# MightyWatt_R3.net
KiCad netlist of a schematic drawn in EAGLE
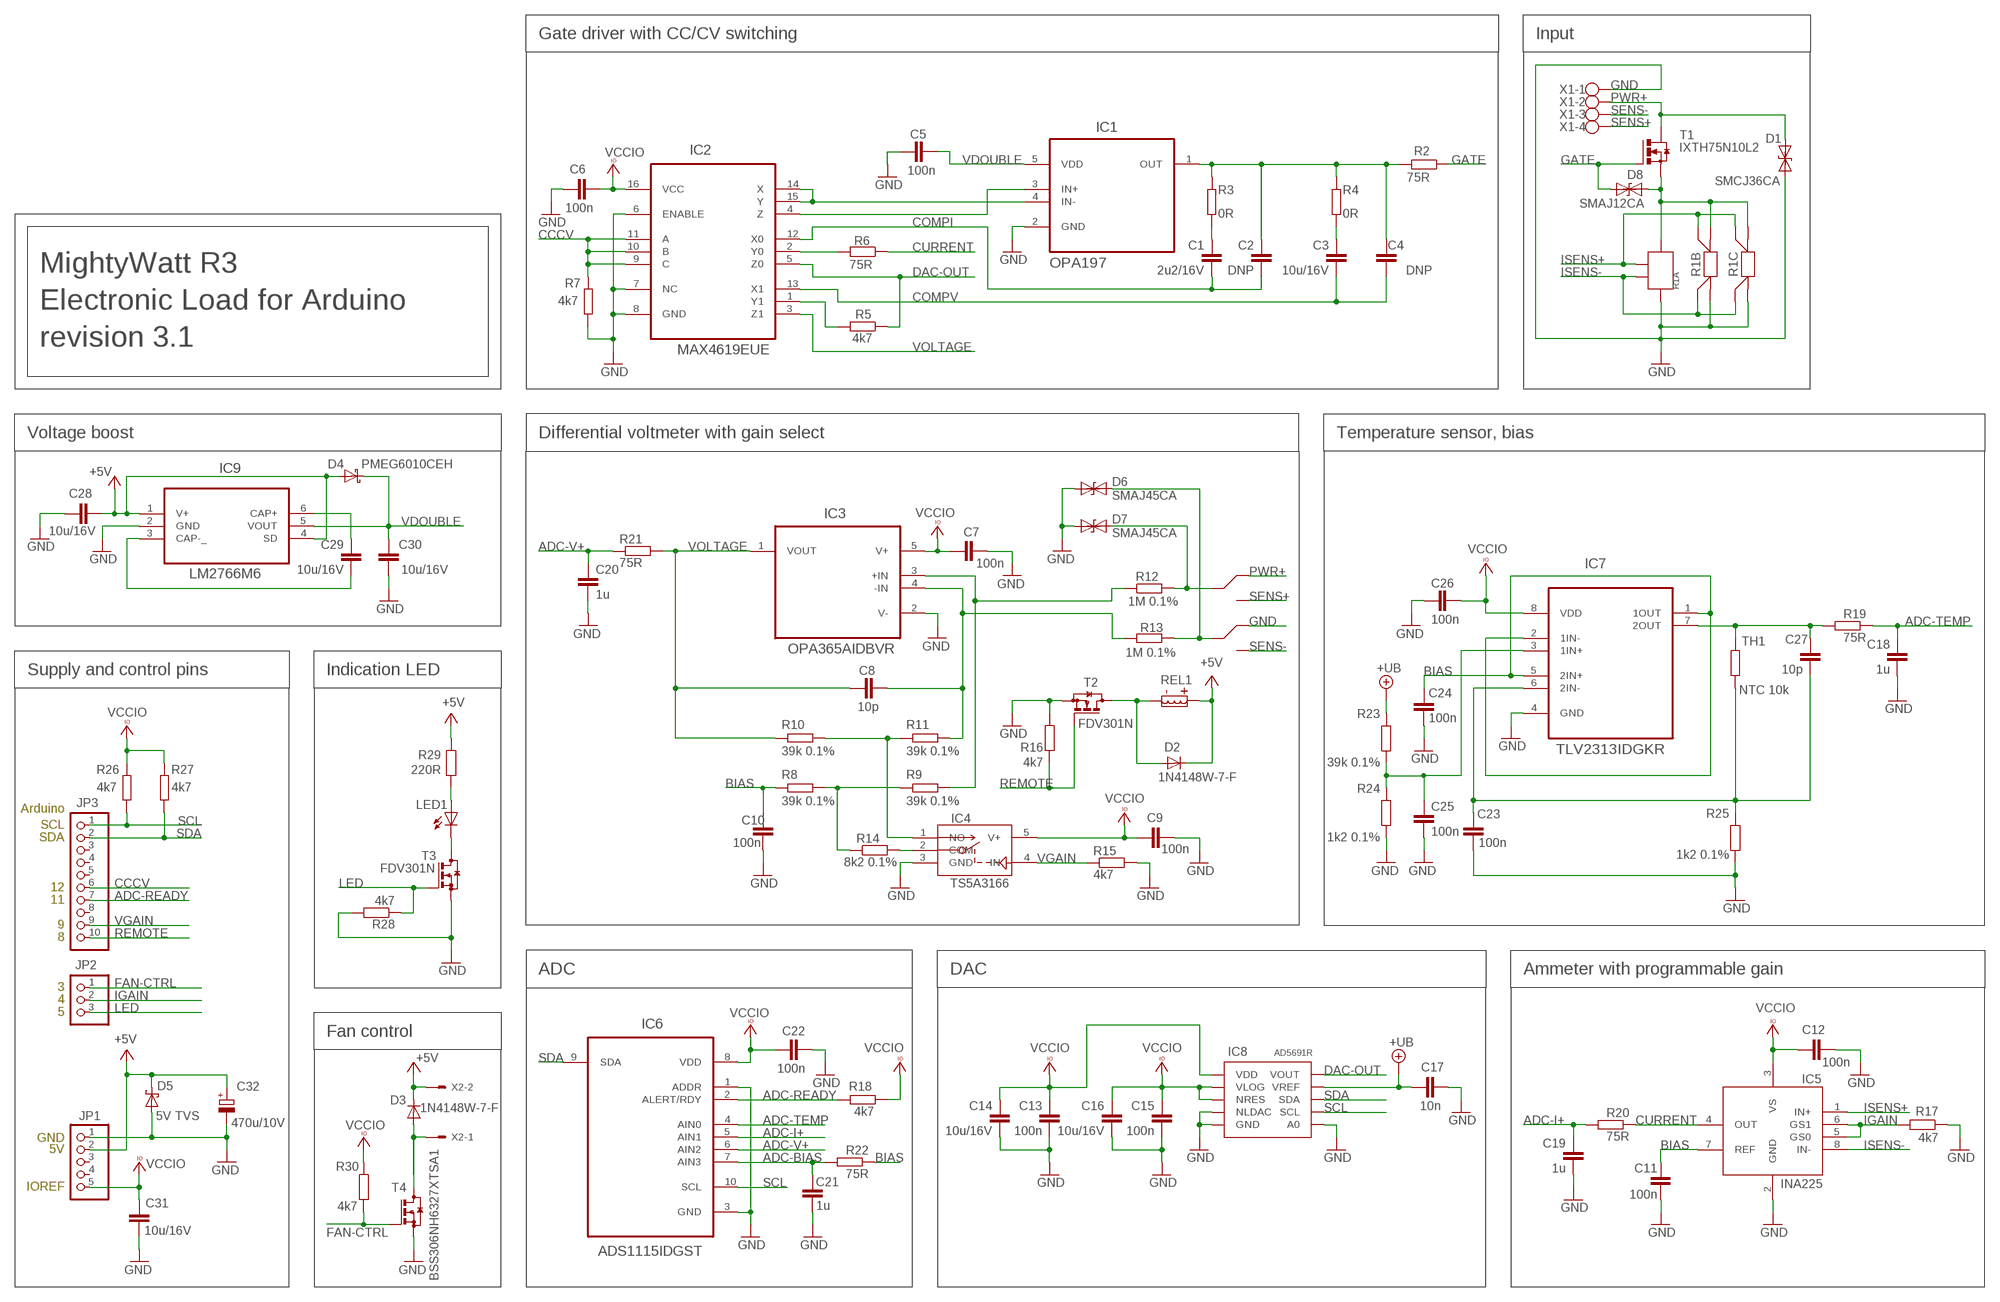
[diagram p0: schematic, sheet 1]

(export (version "E")
  (design (tool "Eeschema 10.0.6"))
  (components
    (comp (ref "C1")
      (value "2u2/16V")
      (footprint "eagle-import:C1206")
      (libsource (lib "eagle-import") (part "C-EUC1206"))
    )
    (comp (ref "C2")
      (value "DNP")
      (footprint "eagle-import:C0603")
      (libsource (lib "eagle-import") (part "C-EUC0603"))
    )
    (comp (ref "C3")
      (value "10u/16V")
      (footprint "eagle-import:C1206")
      (libsource (lib "eagle-import") (part "C-EUC1206"))
    )
    (comp (ref "C4")
      (value "DNP")
      (footprint "eagle-import:C0603")
      (libsource (lib "eagle-import") (part "C-EUC0603"))
    )
    (comp (ref "C5")
      (value "100n")
      (footprint "eagle-import:C0603")
      (libsource (lib "eagle-import") (part "C-EUC0603"))
    )
    (comp (ref "C6")
      (value "100n")
      (footprint "eagle-import:C0603")
      (libsource (lib "eagle-import") (part "C-EUC0603"))
    )
    (comp (ref "C7")
      (value "100n")
      (footprint "eagle-import:C0603")
      (libsource (lib "eagle-import") (part "C-EUC0603"))
    )
    (comp (ref "C8")
      (value "10p")
      (footprint "eagle-import:C0603")
      (libsource (lib "eagle-import") (part "C-EUC0603"))
    )
    (comp (ref "C9")
      (value "100n")
      (footprint "eagle-import:C0603")
      (libsource (lib "eagle-import") (part "C-EUC0603"))
    )
    (comp (ref "C10")
      (value "100n")
      (footprint "eagle-import:C0603")
      (libsource (lib "eagle-import") (part "C-EUC0603"))
    )
    (comp (ref "C11")
      (value "100n")
      (footprint "eagle-import:C0603")
      (libsource (lib "eagle-import") (part "C-EUC0603"))
    )
    (comp (ref "C12")
      (value "100n")
      (footprint "eagle-import:C0603")
      (libsource (lib "eagle-import") (part "C-EUC0603"))
    )
    (comp (ref "C13")
      (value "100n")
      (footprint "eagle-import:C0603")
      (libsource (lib "eagle-import") (part "C-EUC0603"))
    )
    (comp (ref "C14")
      (value "10u/16V")
      (footprint "eagle-import:C1206")
      (libsource (lib "eagle-import") (part "C-EUC1206"))
    )
    (comp (ref "C15")
      (value "100n")
      (footprint "eagle-import:C0603")
      (libsource (lib "eagle-import") (part "C-EUC0603"))
    )
    (comp (ref "C16")
      (value "10u/16V")
      (footprint "eagle-import:C1206")
      (libsource (lib "eagle-import") (part "C-EUC1206"))
    )
    (comp (ref "C17")
      (value "10n")
      (footprint "eagle-import:C0603")
      (libsource (lib "eagle-import") (part "C-EUC0603"))
    )
    (comp (ref "C18")
      (value "1u")
      (footprint "eagle-import:C0603")
      (libsource (lib "eagle-import") (part "C-EUC0603"))
    )
    (comp (ref "C19")
      (value "1u")
      (footprint "eagle-import:C0603")
      (libsource (lib "eagle-import") (part "C-EUC0603"))
    )
    (comp (ref "C20")
      (value "1u")
      (footprint "eagle-import:C0603")
      (libsource (lib "eagle-import") (part "C-EUC0603"))
    )
    (comp (ref "C21")
      (value "1u")
      (footprint "eagle-import:C0603")
      (libsource (lib "eagle-import") (part "C-EUC0603"))
    )
    (comp (ref "C22")
      (value "100n")
      (footprint "eagle-import:C0603")
      (libsource (lib "eagle-import") (part "C-EUC0603"))
    )
    (comp (ref "C23")
      (value "100n")
      (footprint "eagle-import:C0603")
      (libsource (lib "eagle-import") (part "C-EUC0603"))
    )
    (comp (ref "C24")
      (value "100n")
      (footprint "eagle-import:C0603")
      (libsource (lib "eagle-import") (part "C-EUC0603"))
    )
    (comp (ref "C25")
      (value "100n")
      (footprint "eagle-import:C0603")
      (libsource (lib "eagle-import") (part "C-EUC0603"))
    )
    (comp (ref "C26")
      (value "100n")
      (footprint "eagle-import:C0603")
      (libsource (lib "eagle-import") (part "C-EUC0603"))
    )
    (comp (ref "C27")
      (value "10p")
      (footprint "eagle-import:C0603")
      (libsource (lib "eagle-import") (part "C-EUC0603"))
    )
    (comp (ref "C28")
      (value "10u/16V")
      (footprint "eagle-import:C1206")
      (libsource (lib "eagle-import") (part "C-EUC1206"))
    )
    (comp (ref "C29")
      (value "10u/16V")
      (footprint "eagle-import:C1206")
      (libsource (lib "eagle-import") (part "C-EUC1206"))
    )
    (comp (ref "C30")
      (value "10u/16V")
      (footprint "eagle-import:C1206")
      (libsource (lib "eagle-import") (part "C-EUC1206"))
    )
    (comp (ref "C31")
      (value "10u/16V")
      (footprint "eagle-import:C1206")
      (libsource (lib "eagle-import") (part "C-EUC1206"))
    )
    (comp (ref "C32")
      (value "470u/10V")
      (footprint "eagle-import:SMC_E")
      (fields (field (name "PARTN") "TPSB476K010R0250"))
      (libsource (lib "eagle-import") (part "CPOL-EUSMCE"))
    )
    (comp (ref "D1")
      (value "SMCJ36CA")
      (footprint "eagle-import:SMC")
      (libsource (lib "eagle-import") (part "DIODE2SMC"))
    )
    (comp (ref "D2")
      (value "1N4148W-7-F")
      (footprint "eagle-import:SOD123")
      (libsource (lib "eagle-import") (part "DIODE-SOD123"))
    )
    (comp (ref "D3")
      (value "1N4148W-7-F")
      (footprint "eagle-import:SOD123")
      (libsource (lib "eagle-import") (part "DIODE-SOD123"))
    )
    (comp (ref "D4")
      (value "PMEG6010CEH")
      (footprint "eagle-import:SOD123")
      (libsource (lib "eagle-import") (part "diode-schottky_DIODE-SOD123"))
    )
    (comp (ref "D5")
      (value "5V TVS")
      (footprint "eagle-import:SMB")
      (libsource (lib "eagle-import") (part "SCHOTTKY-DIODESMD"))
    )
    (comp (ref "D6")
      (value "SMAJ45CA")
      (footprint "eagle-import:DO-214AC")
      (libsource (lib "eagle-import") (part "DIODE2DO-214AC"))
    )
    (comp (ref "D7")
      (value "SMAJ45CA")
      (footprint "eagle-import:DO-214AC")
      (libsource (lib "eagle-import") (part "DIODE2DO-214AC"))
    )
    (comp (ref "D8")
      (value "SMAJ12CA")
      (footprint "eagle-import:DO-214AC")
      (libsource (lib "eagle-import") (part "DIODE2DO-214AC"))
    )
    (comp (ref "IC1")
      (value "TLV271IDBVR")
      (footprint "eagle-import:SOT95P280X145-5N")
      (fields (field (name "MPN") "TLV271IDBVR") (field (name "MPN_1") "OPA197"))
      (libsource (lib "eagle-import") (part "TLV271IDBVR"))
    )
    (comp (ref "IC2")
      (value "MAX4619EUE")
      (footprint "eagle-import:SOP65P640X120-16N")
      (libsource (lib "eagle-import") (part "MAX4619EUE"))
    )
    (comp (ref "IC3")
      (value "OPA365AIDBVR")
      (footprint "eagle-import:SOT95P280X145-5N")
      (libsource (lib "eagle-import") (part "OPA365AIDBVR"))
    )
    (comp (ref "IC4")
      (value "TS5A3166")
      (footprint "eagle-import:SC70-5")
      (libsource (lib "eagle-import") (part "TS5A3166"))
    )
    (comp (ref "IC5")
      (value "INA225")
      (footprint "eagle-import:MSOP8")
      (libsource (lib "eagle-import") (part "INA225"))
    )
    (comp (ref "IC6")
      (value "ADS1115IDGST")
      (footprint "eagle-import:SOP50P490X110-10N")
      (fields (field (name "MPN") "ADS1015IDGST"))
      (libsource (lib "eagle-import") (part "ADS1115IDGST"))
    )
    (comp (ref "IC7")
      (value "TLV2372IDGK")
      (footprint "eagle-import:SOP65P490X110-8N")
      (fields (field (name "MPN") "TLV2372IDGK") (field (name "MPN_1") "TLV2313IDGKR"))
      (libsource (lib "eagle-import") (part "TLV2372IDGK"))
    )
    (comp (ref "IC8")
      (value "AD5691RAD5691R")
      (footprint "eagle-import:SOP50P490X110-10N")
      (libsource (lib "eagle-import") (part "AD5691RAD5691R"))
    )
    (comp (ref "IC9")
      (value "LM2766M6")
      (footprint "eagle-import:SOT95P285X122-6N")
      (libsource (lib "eagle-import") (part "LM2766M6"))
    )
    (comp (ref "JP1")
      (value "SUPPLY")
      (footprint "eagle-import:1X05")
      (libsource (lib "eagle-import") (part "PINHD-1X5"))
    )
    (comp (ref "JP2")
      (value "CONTROL, LED")
      (footprint "eagle-import:1X03")
      (libsource (lib "eagle-import") (part "PINHD-1X3"))
    )
    (comp (ref "JP3")
      (value "TWI")
      (footprint "eagle-import:1X10")
      (libsource (lib "eagle-import") (part "PINHD-1X10"))
    )
    (comp (ref "LED1")
      (value "LEDCHIP-LED0805")
      (footprint "eagle-import:CHIP-LED0805")
      (libsource (lib "eagle-import") (part "LEDCHIP-LED0805"))
    )
    (comp (ref "R1A")
      (value "WSL3637")
      (footprint "eagle-import:POWER-R-4TERM")
      (libsource (lib "eagle-import") (part "WSL3637"))
    )
    (comp (ref "R1B")
      (value "LVK24")
      (footprint "eagle-import:LVK24")
      (libsource (lib "eagle-import") (part "LVK24"))
    )
    (comp (ref "R1C")
      (value "LVK12")
      (footprint "eagle-import:1206-4WIRE")
      (libsource (lib "eagle-import") (part "LVK12"))
    )
    (comp (ref "R2")
      (value "75R")
      (footprint "eagle-import:R0603")
      (libsource (lib "eagle-import") (part "R-EU_R0603"))
    )
    (comp (ref "R3")
      (value "0R")
      (footprint "eagle-import:R0603")
      (libsource (lib "eagle-import") (part "R-EU_R0603"))
    )
    (comp (ref "R4")
      (value "0R")
      (footprint "eagle-import:R0603")
      (libsource (lib "eagle-import") (part "R-EU_R0603"))
    )
    (comp (ref "R5")
      (value "4k7")
      (footprint "eagle-import:R0603")
      (libsource (lib "eagle-import") (part "R-EU_R0603"))
    )
    (comp (ref "R6")
      (value "75R")
      (footprint "eagle-import:R0603")
      (libsource (lib "eagle-import") (part "R-EU_R0603"))
    )
    (comp (ref "R7")
      (value "4k7")
      (footprint "eagle-import:R0603")
      (libsource (lib "eagle-import") (part "R-EU_R0603"))
    )
    (comp (ref "R8")
      (value "39k 0.1%")
      (footprint "eagle-import:R0603")
      (libsource (lib "eagle-import") (part "R-EU_R0603"))
    )
    (comp (ref "R9")
      (value "39k 0.1%")
      (footprint "eagle-import:R0603")
      (libsource (lib "eagle-import") (part "R-EU_R0603"))
    )
    (comp (ref "R10")
      (value "39k 0.1%")
      (footprint "eagle-import:R0603")
      (libsource (lib "eagle-import") (part "R-EU_R0603"))
    )
    (comp (ref "R11")
      (value "39k 0.1%")
      (footprint "eagle-import:R0603")
      (libsource (lib "eagle-import") (part "R-EU_R0603"))
    )
    (comp (ref "R12")
      (value "1M 0.1%")
      (footprint "eagle-import:R0603")
      (libsource (lib "eagle-import") (part "R-EU_R0603"))
    )
    (comp (ref "R13")
      (value "1M 0.1%")
      (footprint "eagle-import:R0603")
      (libsource (lib "eagle-import") (part "R-EU_R0603"))
    )
    (comp (ref "R14")
      (value "8k2 0.1%")
      (footprint "eagle-import:R0603")
      (libsource (lib "eagle-import") (part "R-EU_R0603"))
    )
    (comp (ref "R15")
      (value "4k7")
      (footprint "eagle-import:R0603")
      (libsource (lib "eagle-import") (part "R-EU_R0603"))
    )
    (comp (ref "R16")
      (value "4k7")
      (footprint "eagle-import:R0603")
      (libsource (lib "eagle-import") (part "R-EU_R0603"))
    )
    (comp (ref "R17")
      (value "4k7")
      (footprint "eagle-import:R0603")
      (libsource (lib "eagle-import") (part "R-EU_R0603"))
    )
    (comp (ref "R18")
      (value "4k7")
      (footprint "eagle-import:R0603")
      (libsource (lib "eagle-import") (part "R-EU_R0603"))
    )
    (comp (ref "R19")
      (value "75R")
      (footprint "eagle-import:R0603")
      (libsource (lib "eagle-import") (part "R-EU_R0603"))
    )
    (comp (ref "R20")
      (value "75R")
      (footprint "eagle-import:R0603")
      (libsource (lib "eagle-import") (part "R-EU_R0603"))
    )
    (comp (ref "R21")
      (value "75R")
      (footprint "eagle-import:R0603")
      (libsource (lib "eagle-import") (part "R-EU_R0603"))
    )
    (comp (ref "R22")
      (value "75R")
      (footprint "eagle-import:R0603")
      (libsource (lib "eagle-import") (part "R-EU_R0603"))
    )
    (comp (ref "R23")
      (value "39k 0.1%")
      (footprint "eagle-import:R0603")
      (libsource (lib "eagle-import") (part "R-EU_R0603"))
    )
    (comp (ref "R24")
      (value "1k2 0.1%")
      (footprint "eagle-import:R0603")
      (libsource (lib "eagle-import") (part "R-EU_R0603"))
    )
    (comp (ref "R25")
      (value "1k2 0.1%")
      (footprint "eagle-import:R0603")
      (libsource (lib "eagle-import") (part "R-EU_R0603"))
    )
    (comp (ref "R26")
      (value "4k7")
      (footprint "eagle-import:R0603")
      (libsource (lib "eagle-import") (part "R-EU_R0603"))
    )
    (comp (ref "R27")
      (value "4k7")
      (footprint "eagle-import:R0603")
      (libsource (lib "eagle-import") (part "R-EU_R0603"))
    )
    (comp (ref "R28")
      (value "4k7")
      (footprint "eagle-import:R0603")
      (libsource (lib "eagle-import") (part "R-EU_R0603"))
    )
    (comp (ref "R29")
      (value "220R")
      (footprint "eagle-import:R0603")
      (libsource (lib "eagle-import") (part "R-EU_R0603"))
    )
    (comp (ref "R30")
      (value "4k7")
      (footprint "eagle-import:R0603")
      (libsource (lib "eagle-import") (part "R-EU_R0603"))
    )
    (comp (ref "REL1")
      (value "IM03NS")
      (footprint "eagle-import:IM03NS-NARROW-RELAY")
      (fields (field (name "REL1") "REL1"))
      (libsource (lib "eagle-import") (part "IM03NS"))
    )
    (comp (ref "T1")
      (value "IXTH75N10L2")
      (footprint "eagle-import:TO247-BLANK")
      (libsource (lib "eagle-import") (part "IXTH75N10L2"))
    )
    (comp (ref "T2")
      (value "BSS123")
      (footprint "eagle-import:SOT23")
      (fields (field (name "PARTNAME") "FDV301N"))
      (libsource (lib "eagle-import") (part "BSS123"))
    )
    (comp (ref "T3")
      (value "BSS123")
      (footprint "eagle-import:SOT23")
      (fields (field (name "PARTNAME") "FDV301N"))
      (libsource (lib "eagle-import") (part "BSS123"))
    )
    (comp (ref "T4")
      (value "BSS123")
      (footprint "eagle-import:SOT23")
      (fields (field (name "PARTNAME") "BSS306NH6327XTSA1"))
      (libsource (lib "eagle-import") (part "BSS123"))
    )
    (comp (ref "TH1")
      (value "NTC 10k")
      (footprint "eagle-import:R0402")
      (libsource (lib "eagle-import") (part "R-EU_R0402"))
    )
    (comp (ref "X1")
      (value "W237-4")
      (footprint "eagle-import:W237-4")
      (libsource (lib "eagle-import") (part "W237-4"))
    )
    (comp (ref "X2")
      (value "22-23-2021")
      (footprint "eagle-import:22-23-2021")
      (fields (field (name "MF") "MOLEX"))
      (libsource (lib "eagle-import") (part "22-23-2021"))
    )
  )
  (nets
    (net (code "1") (name "+5V") (class "Default")
      (node (ref "C28") (pin "1") (pinfunction "1_1") (pintype "passive"))
      (node (ref "C32") (pin "+") (pinfunction "+_+") (pintype "passive"))
      (node (ref "D2") (pin "C") (pinfunction "C_C") (pintype "passive"))
      (node (ref "D3") (pin "C") (pinfunction "C_C") (pintype "passive"))
      (node (ref "D4") (pin "A") (pinfunction "A_A") (pintype "passive"))
      (node (ref "D5") (pin "C") (pinfunction "C_C") (pintype "passive"))
      (node (ref "IC9") (pin "1") (pinfunction "V+_1") (pintype "input"))
      (node (ref "IC9") (pin "4") (pinfunction "SD_4") (pintype "passive"))
      (node (ref "JP1") (pin "2") (pinfunction "2_2") (pintype "passive"))
      (node (ref "R29") (pin "1") (pinfunction "1_1") (pintype "passive"))
      (node (ref "REL1") (pin "P$1") (pinfunction "C+_P$1") (pintype "bidirectional"))
      (node (ref "X2") (pin "2") (pinfunction "S_2") (pintype "passive"))
    )
    (net (code "2") (name "+UB") (class "Default")
      (node (ref "C17") (pin "2") (pinfunction "2_2") (pintype "passive"))
      (node (ref "IC8") (pin "9") (pinfunction "VREF_9") (pintype "bidirectional"))
      (node (ref "R23") (pin "2") (pinfunction "2_2") (pintype "passive"))
    )
    (net (code "3") (name "/ADC-BIAS") (class "Default")
      (node (ref "C21") (pin "2") (pinfunction "2_2") (pintype "passive"))
      (node (ref "IC6") (pin "7") (pinfunction "AIN3_7") (pintype "input"))
      (node (ref "R22") (pin "2") (pinfunction "2_2") (pintype "passive"))
    )
    (net (code "4") (name "/ADC-I+") (class "Default")
      (node (ref "C19") (pin "2") (pinfunction "2_2") (pintype "passive"))
      (node (ref "IC6") (pin "5") (pinfunction "AIN1_5") (pintype "input"))
      (node (ref "R20") (pin "2") (pinfunction "2_2") (pintype "passive"))
    )
    (net (code "5") (name "/ADC-READY") (class "Default")
      (node (ref "IC6") (pin "2") (pinfunction "ALERT/RDY_2") (pintype "input"))
      (node (ref "JP3") (pin "7") (pinfunction "7_7") (pintype "passive"))
      (node (ref "R18") (pin "1") (pinfunction "1_1") (pintype "passive"))
    )
    (net (code "6") (name "/ADC-TEMP") (class "Default")
      (node (ref "C18") (pin "2") (pinfunction "2_2") (pintype "passive"))
      (node (ref "IC6") (pin "4") (pinfunction "AIN0_4") (pintype "input"))
      (node (ref "R19") (pin "1") (pinfunction "1_1") (pintype "passive"))
    )
    (net (code "7") (name "/ADC-V+") (class "Default")
      (node (ref "C20") (pin "2") (pinfunction "2_2") (pintype "passive"))
      (node (ref "IC6") (pin "6") (pinfunction "AIN2_6") (pintype "input"))
      (node (ref "R21") (pin "1") (pinfunction "1_1") (pintype "passive"))
    )
    (net (code "8") (name "/BIAS") (class "Default")
      (node (ref "C10") (pin "2") (pinfunction "2_2") (pintype "passive"))
      (node (ref "C11") (pin "2") (pinfunction "2_2") (pintype "passive"))
      (node (ref "C24") (pin "2") (pinfunction "2_2") (pintype "passive"))
      (node (ref "IC5") (pin "7") (pinfunction "REF_7") (pintype "bidirectional"))
      (node (ref "IC7") (pin "1") (pinfunction "1OUT_1") (pintype "output"))
      (node (ref "IC7") (pin "2") (pinfunction "1IN-_2") (pintype "input"))
      (node (ref "IC7") (pin "5") (pinfunction "2IN+_5") (pintype "input"))
      (node (ref "R22") (pin "1") (pinfunction "1_1") (pintype "passive"))
      (node (ref "R8") (pin "1") (pinfunction "1_1") (pintype "passive"))
    )
    (net (code "9") (name "/CCCV") (class "Default")
      (node (ref "IC2") (pin "10") (pinfunction "B_10") (pintype "input"))
      (node (ref "IC2") (pin "11") (pinfunction "A_11") (pintype "input"))
      (node (ref "IC2") (pin "9") (pinfunction "C_9") (pintype "input"))
      (node (ref "JP3") (pin "6") (pinfunction "6_6") (pintype "passive"))
      (node (ref "R7") (pin "2") (pinfunction "2_2") (pintype "passive"))
    )
    (net (code "10") (name "/COMPI") (class "Default")
      (node (ref "C1") (pin "1") (pinfunction "1_1") (pintype "passive"))
      (node (ref "C2") (pin "1") (pinfunction "1_1") (pintype "passive"))
      (node (ref "IC2") (pin "12") (pinfunction "X0_12") (pintype "bidirectional"))
    )
    (net (code "11") (name "/COMPV") (class "Default")
      (node (ref "C3") (pin "1") (pinfunction "1_1") (pintype "passive"))
      (node (ref "C4") (pin "1") (pinfunction "1_1") (pintype "passive"))
      (node (ref "IC2") (pin "13") (pinfunction "X1_13") (pintype "bidirectional"))
    )
    (net (code "12") (name "/CURRENT") (class "Default")
      (node (ref "IC5") (pin "4") (pinfunction "OUT_4") (pintype "bidirectional"))
      (node (ref "R20") (pin "1") (pinfunction "1_1") (pintype "passive"))
      (node (ref "R6") (pin "1") (pinfunction "1_1") (pintype "passive"))
    )
    (net (code "13") (name "/DAC-OUT") (class "Default")
      (node (ref "IC2") (pin "5") (pinfunction "Z0_5") (pintype "bidirectional"))
      (node (ref "IC8") (pin "10") (pinfunction "VOUT_10") (pintype "bidirectional"))
      (node (ref "R5") (pin "1") (pinfunction "1_1") (pintype "passive"))
    )
    (net (code "14") (name "/FAN-CTRL") (class "Default")
      (node (ref "JP2") (pin "1") (pinfunction "1_1") (pintype "passive"))
      (node (ref "R30") (pin "2") (pinfunction "2_2") (pintype "passive"))
      (node (ref "T4") (pin "1") (pinfunction "G_1") (pintype "passive"))
    )
    (net (code "15") (name "/GATE") (class "Default")
      (node (ref "D8") (pin "C") (pinfunction "C_C") (pintype "passive"))
      (node (ref "R2") (pin "1") (pinfunction "1_1") (pintype "passive"))
      (node (ref "T1") (pin "G") (pinfunction "G_G") (pintype "passive"))
    )
    (net (code "16") (name "/IGAIN") (class "Default")
      (node (ref "IC5") (pin "5") (pinfunction "GS0_5") (pintype "bidirectional"))
      (node (ref "IC5") (pin "6") (pinfunction "GS1_6") (pintype "bidirectional"))
      (node (ref "JP2") (pin "2") (pinfunction "2_2") (pintype "passive"))
      (node (ref "R17") (pin "2") (pinfunction "2_2") (pintype "passive"))
    )
    (net (code "17") (name "/ISENS+") (class "Default")
      (node (ref "IC5") (pin "1") (pinfunction "IN+_1") (pintype "bidirectional"))
      (node (ref "R1A") (pin "SENSE2") (pinfunction "SENSE2_SENSE2") (pintype "bidirectional"))
      (node (ref "R1B") (pin "V2") (pinfunction "V2_V2") (pintype "bidirectional"))
      (node (ref "R1C") (pin "V2") (pinfunction "V2_V2") (pintype "bidirectional"))
    )
    (net (code "18") (name "/ISENS-") (class "Default")
      (node (ref "IC5") (pin "8") (pinfunction "IN-_8") (pintype "bidirectional"))
      (node (ref "R1A") (pin "SENSE1") (pinfunction "SENSE1_SENSE1") (pintype "bidirectional"))
      (node (ref "R1B") (pin "V1") (pinfunction "V1_V1") (pintype "bidirectional"))
      (node (ref "R1C") (pin "V1") (pinfunction "V1_V1") (pintype "bidirectional"))
    )
    (net (code "19") (name "/LED") (class "Default")
      (node (ref "JP2") (pin "3") (pinfunction "3_3") (pintype "passive"))
      (node (ref "R28") (pin "1") (pinfunction "1_1") (pintype "passive"))
      (node (ref "T3") (pin "1") (pinfunction "G_1") (pintype "passive"))
    )
    (net (code "20") (name "/PWR+") (class "Default")
      (node (ref "D1") (pin "C") (pinfunction "C_C") (pintype "passive"))
      (node (ref "REL1") (pin "P$7") (pinfunction "NC_P$7") (pintype "bidirectional"))
      (node (ref "T1") (pin "D") (pinfunction "D_D") (pintype "passive"))
      (node (ref "X1") (pin "2") (pinfunction "KL_2") (pintype "passive"))
    )
    (net (code "21") (name "/REMOTE") (class "Default")
      (node (ref "JP3") (pin "10") (pinfunction "10_10") (pintype "passive"))
      (node (ref "R16") (pin "2") (pinfunction "2_2") (pintype "passive"))
      (node (ref "T2") (pin "1") (pinfunction "G_1") (pintype "passive"))
    )
    (net (code "22") (name "/SCL") (class "Default")
      (node (ref "IC6") (pin "10") (pinfunction "SCL_10") (pintype "input"))
      (node (ref "IC8") (pin "7") (pinfunction "SCL_7") (pintype "bidirectional"))
      (node (ref "JP3") (pin "1") (pinfunction "1_1") (pintype "passive"))
      (node (ref "R26") (pin "1") (pinfunction "1_1") (pintype "passive"))
    )
    (net (code "23") (name "/SDA") (class "Default")
      (node (ref "IC6") (pin "9") (pinfunction "SDA_9") (pintype "bidirectional"))
      (node (ref "IC8") (pin "8") (pinfunction "SDA_8") (pintype "bidirectional"))
      (node (ref "JP3") (pin "2") (pinfunction "2_2") (pintype "passive"))
      (node (ref "R27") (pin "1") (pinfunction "1_1") (pintype "passive"))
    )
    (net (code "24") (name "/SENS+") (class "Default")
      (node (ref "REL1") (pin "P$5") (pinfunction "NO_P$5") (pintype "bidirectional"))
      (node (ref "X1") (pin "4") (pinfunction "KL_4") (pintype "passive"))
    )
    (net (code "25") (name "/SENS-") (class "Default")
      (node (ref "REL1") (pin "P$4") (pinfunction "NO_P$4") (pintype "bidirectional"))
      (node (ref "X1") (pin "3") (pinfunction "KL_3") (pintype "passive"))
    )
    (net (code "26") (name "/VDOUBLE") (class "Default")
      (node (ref "C30") (pin "1") (pinfunction "1_1") (pintype "passive"))
      (node (ref "C5") (pin "2") (pinfunction "2_2") (pintype "passive"))
      (node (ref "D4") (pin "C") (pinfunction "C_C") (pintype "passive"))
      (node (ref "IC1") (pin "5") (pinfunction "VDD_5") (pintype "power_in"))
      (node (ref "IC9") (pin "5") (pinfunction "VOUT_5") (pintype "output"))
    )
    (net (code "27") (name "/VGAIN") (class "Default")
      (node (ref "IC4") (pin "4") (pinfunction "IN_4") (pintype "bidirectional"))
      (node (ref "JP3") (pin "9") (pinfunction "9_9") (pintype "passive"))
      (node (ref "R15") (pin "1") (pinfunction "1_1") (pintype "passive"))
    )
    (net (code "28") (name "/VOLTAGE") (class "Default")
      (node (ref "C8") (pin "1") (pinfunction "1_1") (pintype "passive"))
      (node (ref "IC2") (pin "3") (pinfunction "Z1_3") (pintype "bidirectional"))
      (node (ref "IC3") (pin "1") (pinfunction "VOUT_1") (pintype "output"))
      (node (ref "R10") (pin "1") (pinfunction "1_1") (pintype "passive"))
      (node (ref "R21") (pin "2") (pinfunction "2_2") (pintype "passive"))
    )
    (net (code "29") (name "GND") (class "Default")
      (node (ref "C10") (pin "1") (pinfunction "1_1") (pintype "passive"))
      (node (ref "C11") (pin "1") (pinfunction "1_1") (pintype "passive"))
      (node (ref "C12") (pin "2") (pinfunction "2_2") (pintype "passive"))
      (node (ref "C13") (pin "1") (pinfunction "1_1") (pintype "passive"))
      (node (ref "C14") (pin "2") (pinfunction "2_2") (pintype "passive"))
      (node (ref "C15") (pin "1") (pinfunction "1_1") (pintype "passive"))
      (node (ref "C16") (pin "2") (pinfunction "2_2") (pintype "passive"))
      (node (ref "C17") (pin "1") (pinfunction "1_1") (pintype "passive"))
      (node (ref "C18") (pin "1") (pinfunction "1_1") (pintype "passive"))
      (node (ref "C19") (pin "1") (pinfunction "1_1") (pintype "passive"))
      (node (ref "C20") (pin "1") (pinfunction "1_1") (pintype "passive"))
      (node (ref "C21") (pin "1") (pinfunction "1_1") (pintype "passive"))
      (node (ref "C22") (pin "2") (pinfunction "2_2") (pintype "passive"))
      (node (ref "C23") (pin "1") (pinfunction "1_1") (pintype "passive"))
      (node (ref "C24") (pin "1") (pinfunction "1_1") (pintype "passive"))
      (node (ref "C25") (pin "1") (pinfunction "1_1") (pintype "passive"))
      (node (ref "C26") (pin "2") (pinfunction "2_2") (pintype "passive"))
      (node (ref "C28") (pin "2") (pinfunction "2_2") (pintype "passive"))
      (node (ref "C30") (pin "2") (pinfunction "2_2") (pintype "passive"))
      (node (ref "C31") (pin "2") (pinfunction "2_2") (pintype "passive"))
      (node (ref "C32") (pin "-") (pinfunction "-_-") (pintype "passive"))
      (node (ref "C5") (pin "1") (pinfunction "1_1") (pintype "passive"))
      (node (ref "C6") (pin "2") (pinfunction "2_2") (pintype "passive"))
      (node (ref "C7") (pin "2") (pinfunction "2_2") (pintype "passive"))
      (node (ref "C9") (pin "1") (pinfunction "1_1") (pintype "passive"))
      (node (ref "D1") (pin "A") (pinfunction "A_A") (pintype "passive"))
      (node (ref "D5") (pin "A") (pinfunction "A_A") (pintype "passive"))
      (node (ref "D6") (pin "A") (pinfunction "A_A") (pintype "passive"))
      (node (ref "D7") (pin "A") (pinfunction "A_A") (pintype "passive"))
      (node (ref "IC1") (pin "2") (pinfunction "GND_2") (pintype "passive"))
      (node (ref "IC2") (pin "6") (pinfunction "ENABLE_6") (pintype "input"))
      (node (ref "IC2") (pin "7") (pinfunction "NC_7") (pintype "power_in"))
      (node (ref "IC2") (pin "8") (pinfunction "GND_8") (pintype "passive"))
      (node (ref "IC3") (pin "2") (pinfunction "V-_2") (pintype "power_in"))
      (node (ref "IC4") (pin "3") (pinfunction "GND_3") (pintype "power_in"))
      (node (ref "IC5") (pin "2") (pinfunction "GND_2") (pintype "bidirectional"))
      (node (ref "IC6") (pin "1") (pinfunction "ADDR_1") (pintype "input"))
      (node (ref "IC6") (pin "3") (pinfunction "GND_3") (pintype "passive"))
      (node (ref "IC7") (pin "4") (pinfunction "GND_4") (pintype "passive"))
      (node (ref "IC8") (pin "4") (pinfunction "NLDAC_4") (pintype "bidirectional"))
      (node (ref "IC8") (pin "5") (pinfunction "GND_5") (pintype "bidirectional"))
      (node (ref "IC8") (pin "6") (pinfunction "A0_6") (pintype "bidirectional"))
      (node (ref "IC9") (pin "2") (pinfunction "GND_2") (pintype "passive"))
      (node (ref "JP1") (pin "1") (pinfunction "1_1") (pintype "passive"))
      (node (ref "R15") (pin "2") (pinfunction "2_2") (pintype "passive"))
      (node (ref "R16") (pin "1") (pinfunction "1_1") (pintype "passive"))
      (node (ref "R17") (pin "1") (pinfunction "1_1") (pintype "passive"))
      (node (ref "R1A") (pin "POWER1") (pinfunction "POWER1_POWER1") (pintype "bidirectional"))
      (node (ref "R1B") (pin "I1") (pinfunction "I1_I1") (pintype "bidirectional"))
      (node (ref "R1C") (pin "I1") (pinfunction "I1_I1") (pintype "bidirectional"))
      (node (ref "R24") (pin "1") (pinfunction "1_1") (pintype "passive"))
      (node (ref "R25") (pin "1") (pinfunction "1_1") (pintype "passive"))
      (node (ref "R28") (pin "2") (pinfunction "2_2") (pintype "passive"))
      (node (ref "R7") (pin "1") (pinfunction "1_1") (pintype "passive"))
      (node (ref "REL1") (pin "P$2") (pinfunction "NC_P$2") (pintype "bidirectional"))
      (node (ref "T2") (pin "2") (pinfunction "S_2") (pintype "passive"))
      (node (ref "T3") (pin "2") (pinfunction "S_2") (pintype "passive"))
      (node (ref "T4") (pin "2") (pinfunction "S_2") (pintype "passive"))
      (node (ref "X1") (pin "1") (pinfunction "KL_1") (pintype "passive"))
    )
    (net (code "30") (name "Net-(C1-Pad2)") (class "Default")
      (node (ref "C1") (pin "2") (pinfunction "2_2") (pintype "passive"))
      (node (ref "R3") (pin "2") (pinfunction "2_2") (pintype "passive"))
    )
    (net (code "31") (name "Net-(C3-Pad2)") (class "Default")
      (node (ref "C3") (pin "2") (pinfunction "2_2") (pintype "passive"))
      (node (ref "R4") (pin "2") (pinfunction "2_2") (pintype "passive"))
    )
    (net (code "32") (name "Net-(D8-PadA)") (class "Default")
      (node (ref "D8") (pin "A") (pinfunction "A_A") (pintype "passive"))
      (node (ref "R1A") (pin "POWER2") (pinfunction "POWER2_POWER2") (pintype "bidirectional"))
      (node (ref "R1B") (pin "I2") (pinfunction "I2_I2") (pintype "bidirectional"))
      (node (ref "R1C") (pin "I2") (pinfunction "I2_I2") (pintype "bidirectional"))
      (node (ref "T1") (pin "S") (pinfunction "S_S") (pintype "passive"))
    )
    (net (code "33") (name "Net-(IC1-IN+)") (class "Default")
      (node (ref "IC1") (pin "3") (pinfunction "IN+_3") (pintype "input"))
      (node (ref "IC2") (pin "4") (pinfunction "Z_4") (pintype "bidirectional"))
    )
    (net (code "34") (name "Net-(IC1-IN-)") (class "Default")
      (node (ref "IC1") (pin "4") (pinfunction "IN-_4") (pintype "input"))
      (node (ref "IC2") (pin "14") (pinfunction "X_14") (pintype "bidirectional"))
      (node (ref "IC2") (pin "15") (pinfunction "Y_15") (pintype "bidirectional"))
    )
    (net (code "35") (name "Net-(IC1-OUT)") (class "Default")
      (node (ref "C2") (pin "2") (pinfunction "2_2") (pintype "passive"))
      (node (ref "C4") (pin "2") (pinfunction "2_2") (pintype "passive"))
      (node (ref "IC1") (pin "1") (pinfunction "OUT_1") (pintype "output"))
      (node (ref "R2") (pin "2") (pinfunction "2_2") (pintype "passive"))
      (node (ref "R3") (pin "1") (pinfunction "1_1") (pintype "passive"))
      (node (ref "R4") (pin "1") (pinfunction "1_1") (pintype "passive"))
    )
    (net (code "36") (name "Net-(IC2-Y0)") (class "Default")
      (node (ref "IC2") (pin "2") (pinfunction "Y0_2") (pintype "bidirectional"))
      (node (ref "R6") (pin "2") (pinfunction "2_2") (pintype "passive"))
    )
    (net (code "37") (name "Net-(IC2-Y1)") (class "Default")
      (node (ref "IC2") (pin "1") (pinfunction "Y1_1") (pintype "bidirectional"))
      (node (ref "R5") (pin "2") (pinfunction "2_2") (pintype "passive"))
    )
    (net (code "38") (name "Net-(IC3-+IN)") (class "Default")
      (node (ref "IC3") (pin "3") (pinfunction "+IN_3") (pintype "input"))
      (node (ref "R12") (pin "1") (pinfunction "1_1") (pintype "passive"))
      (node (ref "R9") (pin "2") (pinfunction "2_2") (pintype "passive"))
    )
    (net (code "39") (name "Net-(IC3--IN)") (class "Default")
      (node (ref "C8") (pin "2") (pinfunction "2_2") (pintype "passive"))
      (node (ref "IC3") (pin "4") (pinfunction "-IN_4") (pintype "input"))
      (node (ref "R11") (pin "2") (pinfunction "2_2") (pintype "passive"))
      (node (ref "R13") (pin "2") (pinfunction "2_2") (pintype "passive"))
    )
    (net (code "40") (name "Net-(IC4-COM)") (class "Default")
      (node (ref "IC4") (pin "2") (pinfunction "COM_2") (pintype "output"))
      (node (ref "R14") (pin "2") (pinfunction "2_2") (pintype "passive"))
    )
    (net (code "41") (name "Net-(IC4-NO)") (class "Default")
      (node (ref "IC4") (pin "1") (pinfunction "NO_1") (pintype "input"))
      (node (ref "R10") (pin "2") (pinfunction "2_2") (pintype "passive"))
      (node (ref "R11") (pin "1") (pinfunction "1_1") (pintype "passive"))
    )
    (net (code "42") (name "Net-(IC7-1IN+)") (class "Default")
      (node (ref "C25") (pin "2") (pinfunction "2_2") (pintype "passive"))
      (node (ref "IC7") (pin "3") (pinfunction "1IN+_3") (pintype "input"))
      (node (ref "R23") (pin "1") (pinfunction "1_1") (pintype "passive"))
      (node (ref "R24") (pin "2") (pinfunction "2_2") (pintype "passive"))
    )
    (net (code "43") (name "Net-(IC7-2IN-)") (class "Default")
      (node (ref "C23") (pin "2") (pinfunction "2_2") (pintype "passive"))
      (node (ref "C27") (pin "1") (pinfunction "1_1") (pintype "passive"))
      (node (ref "IC7") (pin "6") (pinfunction "2IN-_6") (pintype "input"))
      (node (ref "R25") (pin "2") (pinfunction "2_2") (pintype "passive"))
      (node (ref "TH1") (pin "1") (pinfunction "1_1") (pintype "passive"))
    )
    (net (code "44") (name "Net-(IC7-2OUT)") (class "Default")
      (node (ref "C27") (pin "2") (pinfunction "2_2") (pintype "passive"))
      (node (ref "IC7") (pin "7") (pinfunction "2OUT_7") (pintype "output"))
      (node (ref "R19") (pin "2") (pinfunction "2_2") (pintype "passive"))
      (node (ref "TH1") (pin "2") (pinfunction "2_2") (pintype "passive"))
    )
    (net (code "45") (name "Net-(IC9-CAP+)") (class "Default")
      (node (ref "C29") (pin "1") (pinfunction "1_1") (pintype "passive"))
      (node (ref "IC9") (pin "6") (pinfunction "CAP+_6") (pintype "passive"))
    )
    (net (code "46") (name "Net-(IC9-CAP-_)") (class "Default")
      (node (ref "C29") (pin "2") (pinfunction "2_2") (pintype "passive"))
      (node (ref "IC9") (pin "3") (pinfunction "CAP-__3") (pintype "passive"))
    )
    (net (code "47") (name "Net-(LED1-PadA)") (class "Default")
      (node (ref "LED1") (pin "A") (pinfunction "A_A") (pintype "passive"))
      (node (ref "R29") (pin "2") (pinfunction "2_2") (pintype "passive"))
    )
    (net (code "48") (name "Net-(R14-Pad1)") (class "Default")
      (node (ref "R14") (pin "1") (pinfunction "1_1") (pintype "passive"))
      (node (ref "R8") (pin "2") (pinfunction "2_2") (pintype "passive"))
      (node (ref "R9") (pin "1") (pinfunction "1_1") (pintype "passive"))
    )
    (net (code "49") (name "Net-(REL1A-C-)") (class "Default")
      (node (ref "D2") (pin "A") (pinfunction "A_A") (pintype "passive"))
      (node (ref "REL1") (pin "P$8") (pinfunction "C-_P$8") (pintype "bidirectional"))
      (node (ref "T2") (pin "3") (pinfunction "D_3") (pintype "passive"))
    )
    (net (code "50") (name "Net-(REL1B-COM)") (class "Default")
      (node (ref "D6") (pin "C") (pinfunction "C_C") (pintype "passive"))
      (node (ref "R13") (pin "1") (pinfunction "1_1") (pintype "passive"))
      (node (ref "REL1") (pin "P$3") (pinfunction "COM_P$3") (pintype "bidirectional"))
    )
    (net (code "51") (name "Net-(REL1C-COM)") (class "Default")
      (node (ref "D7") (pin "C") (pinfunction "C_C") (pintype "passive"))
      (node (ref "R12") (pin "2") (pinfunction "2_2") (pintype "passive"))
      (node (ref "REL1") (pin "P$6") (pinfunction "COM_P$6") (pintype "bidirectional"))
    )
    (net (code "52") (name "Net-(T3-D)") (class "Default")
      (node (ref "LED1") (pin "C") (pinfunction "C_C") (pintype "passive"))
      (node (ref "T3") (pin "3") (pinfunction "D_3") (pintype "passive"))
    )
    (net (code "53") (name "Net-(T4-D)") (class "Default")
      (node (ref "D3") (pin "A") (pinfunction "A_A") (pintype "passive"))
      (node (ref "T4") (pin "3") (pinfunction "D_3") (pintype "passive"))
      (node (ref "X2") (pin "1") (pinfunction "S_1") (pintype "passive"))
    )
    (net (code "54") (name "VCCIO") (class "Default")
      (node (ref "C12") (pin "1") (pinfunction "1_1") (pintype "passive"))
      (node (ref "C13") (pin "2") (pinfunction "2_2") (pintype "passive"))
      (node (ref "C14") (pin "1") (pinfunction "1_1") (pintype "passive"))
      (node (ref "C15") (pin "2") (pinfunction "2_2") (pintype "passive"))
      (node (ref "C16") (pin "1") (pinfunction "1_1") (pintype "passive"))
      (node (ref "C22") (pin "1") (pinfunction "1_1") (pintype "passive"))
      (node (ref "C26") (pin "1") (pinfunction "1_1") (pintype "passive"))
      (node (ref "C31") (pin "1") (pinfunction "1_1") (pintype "passive"))
      (node (ref "C6") (pin "1") (pinfunction "1_1") (pintype "passive"))
      (node (ref "C7") (pin "1") (pinfunction "1_1") (pintype "passive"))
      (node (ref "C9") (pin "2") (pinfunction "2_2") (pintype "passive"))
      (node (ref "IC2") (pin "16") (pinfunction "VCC_16") (pintype "power_in"))
      (node (ref "IC3") (pin "5") (pinfunction "V+_5") (pintype "power_in"))
      (node (ref "IC4") (pin "5") (pinfunction "V+_5") (pintype "power_in"))
      (node (ref "IC5") (pin "3") (pinfunction "VS_3") (pintype "bidirectional"))
      (node (ref "IC6") (pin "8") (pinfunction "VDD_8") (pintype "power_in"))
      (node (ref "IC7") (pin "8") (pinfunction "VDD_8") (pintype "power_in"))
      (node (ref "IC8") (pin "1") (pinfunction "VDD_1") (pintype "bidirectional"))
      (node (ref "IC8") (pin "2") (pinfunction "VLOG_2") (pintype "bidirectional"))
      (node (ref "IC8") (pin "3") (pinfunction "NRES_3") (pintype "bidirectional"))
      (node (ref "JP1") (pin "5") (pinfunction "5_5") (pintype "passive"))
      (node (ref "R18") (pin "2") (pinfunction "2_2") (pintype "passive"))
      (node (ref "R26") (pin "2") (pinfunction "2_2") (pintype "passive"))
      (node (ref "R27") (pin "2") (pinfunction "2_2") (pintype "passive"))
      (node (ref "R30") (pin "1") (pinfunction "1_1") (pintype "passive"))
    )
    (net (code "55") (name "unconnected-(JP1-Pad3)") (class "Default")
      (node (ref "JP1") (pin "3") (pinfunction "3_3") (pintype "passive"))
    )
    (net (code "56") (name "unconnected-(JP1-Pad4)") (class "Default")
      (node (ref "JP1") (pin "4") (pinfunction "4_4") (pintype "passive"))
    )
    (net (code "57") (name "unconnected-(JP3-Pad3)") (class "Default")
      (node (ref "JP3") (pin "3") (pinfunction "3_3") (pintype "passive"))
    )
    (net (code "58") (name "unconnected-(JP3-Pad4)") (class "Default")
      (node (ref "JP3") (pin "4") (pinfunction "4_4") (pintype "passive"))
    )
    (net (code "59") (name "unconnected-(JP3-Pad5)") (class "Default")
      (node (ref "JP3") (pin "5") (pinfunction "5_5") (pintype "passive"))
    )
    (net (code "60") (name "unconnected-(JP3-Pad8)") (class "Default")
      (node (ref "JP3") (pin "8") (pinfunction "8_8") (pintype "passive"))
    )
  )
)
